# Gambar_Teknik_EAGLE_DRAJAD_PAMUNGKAS.net
KiCad netlist of a schematic drawn in EAGLE
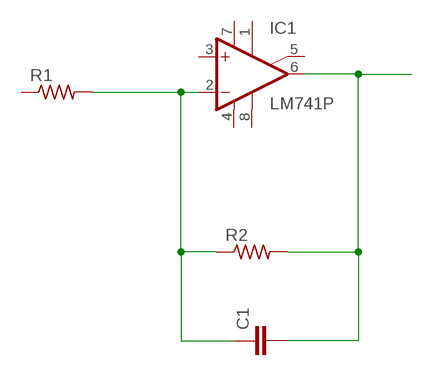
[diagram p0: schematic, sheet 1]

(export (version "E")
  (design (tool "Eeschema 10.0.6"))
  (components
    (comp (ref "C1")
      (value "C2,5-3")
      (footprint "eagle-import:C2.5-3")
      (libsource (lib "eagle-import") (part "C2,5-3"))
    )
    (comp (ref "IC1")
      (value "LM741P")
      (footprint "eagle-import:DIL08")
      (libsource (lib "eagle-import") (part "741PLM"))
    )
    (comp (ref "R1")
      (value "R-US_0204/2V")
      (footprint "eagle-import:0204V")
      (libsource (lib "eagle-import") (part "R-US_0204/2V"))
    )
    (comp (ref "R2")
      (value "R-US_0204/2V")
      (footprint "eagle-import:0204V")
      (libsource (lib "eagle-import") (part "R-US_0204/2V"))
    )
  )
  (nets
    (net (code "1") (name "/V+") (class "Default")
      (node (ref "IC1") (pin "7") (pinfunction "V+_7") (pintype "power_in"))
    )
    (net (code "2") (name "/V-") (class "Default")
      (node (ref "IC1") (pin "4") (pinfunction "V-_4") (pintype "power_in"))
    )
    (net (code "3") (name "Net-(IC1--IN)") (class "Default")
      (node (ref "C1") (pin "1") (pinfunction "1_1") (pintype "passive"))
      (node (ref "IC1") (pin "2") (pinfunction "-IN_2") (pintype "input"))
      (node (ref "R1") (pin "2") (pinfunction "2_2") (pintype "passive"))
      (node (ref "R2") (pin "1") (pinfunction "1_1") (pintype "passive"))
    )
    (net (code "4") (name "Net-(IC1-OUT)") (class "Default")
      (node (ref "C1") (pin "2") (pinfunction "2_2") (pintype "passive"))
      (node (ref "IC1") (pin "6") (pinfunction "OUT_6") (pintype "output"))
      (node (ref "R2") (pin "2") (pinfunction "2_2") (pintype "passive"))
    )
    (net (code "5") (name "unconnected-(IC1-+IN-Pad3)") (class "Default")
      (node (ref "IC1") (pin "3") (pinfunction "+IN_3") (pintype "input"))
    )
    (net (code "6") (name "unconnected-(IC1-ON1-Pad1)") (class "Default")
      (node (ref "IC1") (pin "1") (pinfunction "ON1_1") (pintype "passive"))
    )
    (net (code "7") (name "unconnected-(IC1-ON2-Pad5)") (class "Default")
      (node (ref "IC1") (pin "5") (pinfunction "ON2_5") (pintype "passive"))
    )
    (net (code "8") (name "unconnected-(IC1-OPT-Pad8)") (class "Default")
      (node (ref "IC1") (pin "8") (pinfunction "OPT_8") (pintype "passive"))
    )
    (net (code "9") (name "unconnected-(R1-Pad1)") (class "Default")
      (node (ref "R1") (pin "1") (pinfunction "1_1") (pintype "passive"))
    )
  )
)
